# PilotPi_Sensors.net
KiCad netlist of a schematic drawn in Altium Designer
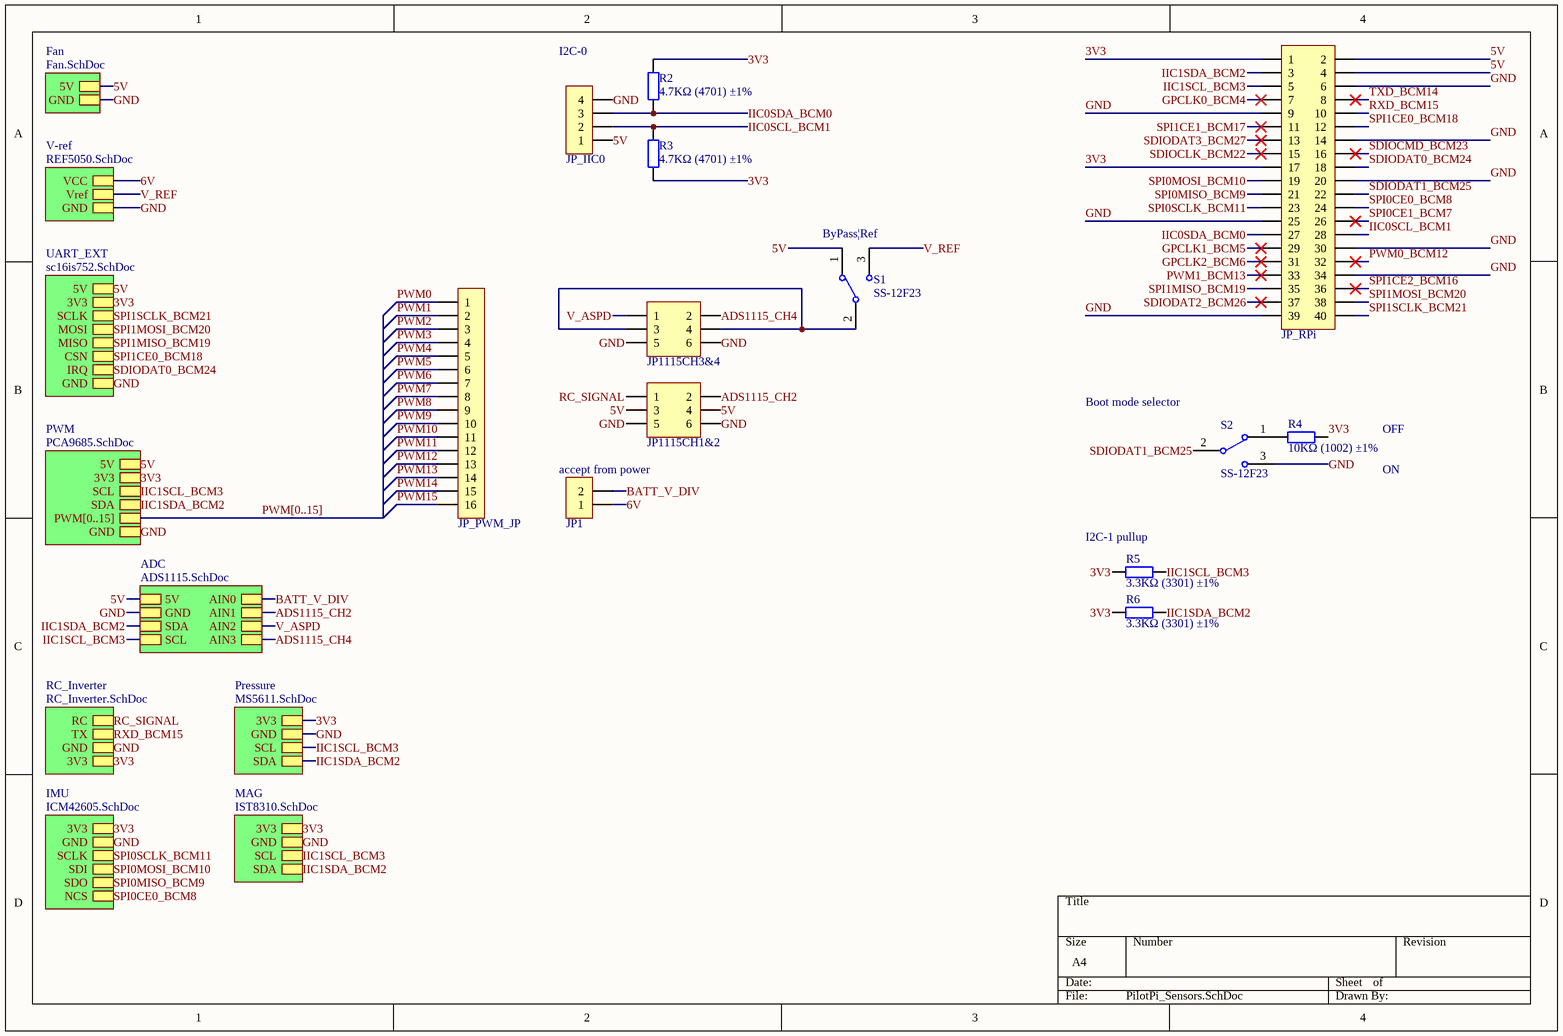
[diagram p0: PilotPi_Sensors.SchDoc]

(export (version "E")
  (design (tool "Eeschema 10.0.6"))
  (components
    (comp (ref "JP1")
      (value "HDR-1X2")
      (footprint "HDR2.54-LI-2P")
      (description "2P接插件")
      (fields (field (name "版权归属") "源创客"))
      (libsource (lib "4.5   - 接插件-脚距2.54") (part "Header 2"))
    )
    (comp (ref "JP1115CH1&2")
      (value "Header3X2")
      (footprint "HDR2.54-WI-2x3P")
      (description "3*2P接插件")
      (fields (field (name "版权归属") "源创客"))
      (libsource (lib "4.5   - 接插件-脚距2.54") (part "Header 3X2"))
    )
    (comp (ref "JP1115CH3&4")
      (value "Header3X2")
      (footprint "HDR2.54-WI-2x3P")
      (description "3*2P接插件")
      (fields (field (name "版权归属") "源创客"))
      (libsource (lib "4.5   - 接插件-脚距2.54") (part "Header 3X2"))
    )
    (comp (ref "JP_IIC0")
      (value "HDR-1X4")
      (footprint "MX 1.25-WS-4P")
      (description "4P接插件")
      (fields (field (name "版权归属") "源创客"))
      (libsource (lib "4.2   - 接插件-脚距1.25") (part "Header 4"))
    )
    (comp (ref "JP_PWM_JP")
      (value "HDR-1X16")
      (footprint "HDR2.54-LI-16P")
      (description "16P接插件")
      (fields (field (name "版权归属") "源创客"))
      (libsource (lib "4.5   - 接插件-脚距2.54") (part "Header 16"))
    )
    (comp (ref "JP_RPi")
      (value "Header 2X11")
      (footprint "HDR2.54-LI-2x20P")
      (description "20*2P接插件")
      (fields (field (name "版权归属") "源创客"))
      (libsource (lib "4.5   - 接插件-脚距2.54") (part "Header 20X2"))
    )
    (comp (ref "R2")
      (value "4.7KΩ (4701) ±1%")
      (footprint "0402_R")
      (description "贴片电阻")
      (libsource (lib "Miscellaneous Devices LC") (part "0402 4.7KΩ (4701) 1%"))
    )
    (comp (ref "R3")
      (value "4.7KΩ (4701) ±1%")
      (footprint "0402_R")
      (description "贴片电阻")
      (libsource (lib "Miscellaneous Devices LC") (part "0402 4.7KΩ (4701) 1%"))
    )
    (comp (ref "R4")
      (value "10KΩ (1002) ±1%")
      (footprint "0402_R")
      (description "贴片电阻")
      (libsource (lib "Miscellaneous Devices LC") (part "0402 10KΩ (1002) 1%"))
    )
    (comp (ref "R5")
      (value "3.3KΩ (3301) ±1%")
      (footprint "0402_R")
      (description "贴片电阻")
      (libsource (lib "Miscellaneous Devices LC") (part "0402 3.3KΩ (3301) 1%"))
    )
    (comp (ref "R6")
      (value "3.3KΩ (3301) ±1%")
      (footprint "0402_R")
      (description "贴片电阻")
      (libsource (lib "Miscellaneous Devices LC") (part "0402 3.3KΩ (3301) 1%"))
    )
    (comp (ref "S1")
      (value "SS-12F23")
      (footprint "MSK-12C01-07")
      (description "1路波动开关")
      (fields (field (name "版权归属") "源创客"))
      (libsource (lib "5.1   - 按键-开关") (part "SSW-1P"))
    )
    (comp (ref "S2")
      (value "SS-12F23")
      (footprint "MSK-12C01-07")
      (description "1路波动开关")
      (fields (field (name "版权归属") "源创客"))
      (libsource (lib "5.1   - 按键-开关") (part "SSW-1P"))
    )
  )
  (nets
    (net (code "1") (name "/3V3") (class "Default")
      (node (ref "JP_RPi") (pin "1") (pinfunction "1_1") (pintype "passive"))
      (node (ref "JP_RPi") (pin "17") (pinfunction "17_17") (pintype "passive"))
      (node (ref "R2") (pin "2") (pinfunction "2_2") (pintype "passive"))
      (node (ref "R3") (pin "1") (pinfunction "1_1") (pintype "passive"))
      (node (ref "R4") (pin "2") (pinfunction "2_2") (pintype "passive"))
      (node (ref "R5") (pin "1") (pinfunction "1_1") (pintype "passive"))
      (node (ref "R6") (pin "1") (pinfunction "1_1") (pintype "passive"))
    )
    (net (code "2") (name "/5V") (class "Default")
      (node (ref "JP1115CH1&2") (pin "3") (pinfunction "3_3") (pintype "passive"))
      (node (ref "JP1115CH1&2") (pin "4") (pinfunction "4_4") (pintype "passive"))
      (node (ref "JP_IIC0") (pin "1") (pinfunction "1_1") (pintype "passive"))
      (node (ref "JP_RPi") (pin "2") (pinfunction "2_2") (pintype "passive"))
      (node (ref "JP_RPi") (pin "4") (pinfunction "4_4") (pintype "passive"))
      (node (ref "S1") (pin "1") (pinfunction "1_1") (pintype "passive"))
    )
    (net (code "3") (name "/6V") (class "Default")
      (node (ref "JP1") (pin "1") (pinfunction "1_1") (pintype "passive"))
    )
    (net (code "4") (name "/ADS1115_CH2") (class "Default")
      (node (ref "JP1115CH1&2") (pin "2") (pinfunction "2_2") (pintype "passive"))
    )
    (net (code "5") (name "/ADS1115_CH4") (class "Default")
      (node (ref "JP1115CH3&4") (pin "2") (pinfunction "2_2") (pintype "passive"))
    )
    (net (code "6") (name "/BATT_V_DIV") (class "Default")
      (node (ref "JP1") (pin "2") (pinfunction "2_2") (pintype "passive"))
    )
    (net (code "7") (name "/GND") (class "Default")
      (node (ref "JP1115CH1&2") (pin "5") (pinfunction "5_5") (pintype "passive"))
      (node (ref "JP1115CH1&2") (pin "6") (pinfunction "6_6") (pintype "passive"))
      (node (ref "JP1115CH3&4") (pin "5") (pinfunction "5_5") (pintype "passive"))
      (node (ref "JP1115CH3&4") (pin "6") (pinfunction "6_6") (pintype "passive"))
      (node (ref "JP_IIC0") (pin "4") (pinfunction "4_4") (pintype "passive"))
      (node (ref "JP_RPi") (pin "14") (pinfunction "14_14") (pintype "passive"))
      (node (ref "JP_RPi") (pin "20") (pinfunction "20_20") (pintype "passive"))
      (node (ref "JP_RPi") (pin "25") (pinfunction "25_25") (pintype "passive"))
      (node (ref "JP_RPi") (pin "30") (pinfunction "30_30") (pintype "passive"))
      (node (ref "JP_RPi") (pin "34") (pinfunction "34_34") (pintype "passive"))
      (node (ref "JP_RPi") (pin "39") (pinfunction "39_39") (pintype "passive"))
      (node (ref "JP_RPi") (pin "6") (pinfunction "6_6") (pintype "passive"))
      (node (ref "JP_RPi") (pin "9") (pinfunction "9_9") (pintype "passive"))
      (node (ref "S2") (pin "3") (pinfunction "3_3") (pintype "passive"))
    )
    (net (code "8") (name "/GPCLK0_BCM4") (class "Default")
      (node (ref "JP_RPi") (pin "7") (pinfunction "7_7") (pintype "passive+no_connect"))
    )
    (net (code "9") (name "/GPCLK1_BCM5") (class "Default")
      (node (ref "JP_RPi") (pin "29") (pinfunction "29_29") (pintype "passive+no_connect"))
    )
    (net (code "10") (name "/GPCLK2_BCM6") (class "Default")
      (node (ref "JP_RPi") (pin "31") (pinfunction "31_31") (pintype "passive+no_connect"))
    )
    (net (code "11") (name "/IIC0SCL_BCM1") (class "Default")
      (node (ref "JP_IIC0") (pin "2") (pinfunction "2_2") (pintype "passive"))
      (node (ref "JP_RPi") (pin "28") (pinfunction "28_28") (pintype "passive"))
      (node (ref "R3") (pin "2") (pinfunction "2_2") (pintype "passive"))
    )
    (net (code "12") (name "/IIC0SDA_BCM0") (class "Default")
      (node (ref "JP_IIC0") (pin "3") (pinfunction "3_3") (pintype "passive"))
      (node (ref "JP_RPi") (pin "27") (pinfunction "27_27") (pintype "passive"))
      (node (ref "R2") (pin "1") (pinfunction "1_1") (pintype "passive"))
    )
    (net (code "13") (name "/IIC1SCL_BCM3") (class "Default")
      (node (ref "JP_RPi") (pin "5") (pinfunction "5_5") (pintype "passive"))
      (node (ref "R5") (pin "2") (pinfunction "2_2") (pintype "passive"))
    )
    (net (code "14") (name "/IIC1SDA_BCM2") (class "Default")
      (node (ref "JP_RPi") (pin "3") (pinfunction "3_3") (pintype "passive"))
      (node (ref "R6") (pin "2") (pinfunction "2_2") (pintype "passive"))
    )
    (net (code "15") (name "/PWM0") (class "Default")
      (node (ref "JP_PWM_JP") (pin "1") (pinfunction "1_1") (pintype "passive"))
    )
    (net (code "16") (name "/PWM0_BCM12") (class "Default")
      (node (ref "JP_RPi") (pin "32") (pinfunction "32_32") (pintype "passive+no_connect"))
    )
    (net (code "17") (name "/PWM1") (class "Default")
      (node (ref "JP_PWM_JP") (pin "2") (pinfunction "2_2") (pintype "passive"))
    )
    (net (code "18") (name "/PWM1_BCM13") (class "Default")
      (node (ref "JP_RPi") (pin "33") (pinfunction "33_33") (pintype "passive+no_connect"))
    )
    (net (code "19") (name "/PWM2") (class "Default")
      (node (ref "JP_PWM_JP") (pin "3") (pinfunction "3_3") (pintype "passive"))
    )
    (net (code "20") (name "/PWM3") (class "Default")
      (node (ref "JP_PWM_JP") (pin "4") (pinfunction "4_4") (pintype "passive"))
    )
    (net (code "21") (name "/PWM4") (class "Default")
      (node (ref "JP_PWM_JP") (pin "5") (pinfunction "5_5") (pintype "passive"))
    )
    (net (code "22") (name "/PWM5") (class "Default")
      (node (ref "JP_PWM_JP") (pin "6") (pinfunction "6_6") (pintype "passive"))
    )
    (net (code "23") (name "/PWM6") (class "Default")
      (node (ref "JP_PWM_JP") (pin "7") (pinfunction "7_7") (pintype "passive"))
    )
    (net (code "24") (name "/PWM7") (class "Default")
      (node (ref "JP_PWM_JP") (pin "8") (pinfunction "8_8") (pintype "passive"))
    )
    (net (code "25") (name "/PWM8") (class "Default")
      (node (ref "JP_PWM_JP") (pin "9") (pinfunction "9_9") (pintype "passive"))
    )
    (net (code "26") (name "/PWM9") (class "Default")
      (node (ref "JP_PWM_JP") (pin "10") (pinfunction "10_10") (pintype "passive"))
    )
    (net (code "27") (name "/PWM10") (class "Default")
      (node (ref "JP_PWM_JP") (pin "11") (pinfunction "11_11") (pintype "passive"))
    )
    (net (code "28") (name "/PWM11") (class "Default")
      (node (ref "JP_PWM_JP") (pin "12") (pinfunction "12_12") (pintype "passive"))
    )
    (net (code "29") (name "/PWM12") (class "Default")
      (node (ref "JP_PWM_JP") (pin "13") (pinfunction "13_13") (pintype "passive"))
    )
    (net (code "30") (name "/PWM13") (class "Default")
      (node (ref "JP_PWM_JP") (pin "14") (pinfunction "14_14") (pintype "passive"))
    )
    (net (code "31") (name "/PWM14") (class "Default")
      (node (ref "JP_PWM_JP") (pin "15") (pinfunction "15_15") (pintype "passive"))
    )
    (net (code "32") (name "/PWM15") (class "Default")
      (node (ref "JP_PWM_JP") (pin "16") (pinfunction "16_16") (pintype "passive"))
    )
    (net (code "34") (name "/RC_SIGNAL") (class "Default")
      (node (ref "JP1115CH1&2") (pin "1") (pinfunction "1_1") (pintype "passive"))
    )
    (net (code "35") (name "/RXD_BCM15") (class "Default")
      (node (ref "JP_RPi") (pin "10") (pinfunction "10_10") (pintype "passive"))
    )
    (net (code "36") (name "/SDIOCLK_BCM22") (class "Default")
      (node (ref "JP_RPi") (pin "15") (pinfunction "15_15") (pintype "passive+no_connect"))
    )
    (net (code "37") (name "/SDIOCMD_BCM23") (class "Default")
      (node (ref "JP_RPi") (pin "16") (pinfunction "16_16") (pintype "passive+no_connect"))
    )
    (net (code "38") (name "/SDIODAT0_BCM24") (class "Default")
      (node (ref "JP_RPi") (pin "18") (pinfunction "18_18") (pintype "passive"))
    )
    (net (code "39") (name "/SDIODAT1_BCM25") (class "Default")
      (node (ref "JP_RPi") (pin "22") (pinfunction "22_22") (pintype "passive"))
      (node (ref "S2") (pin "2") (pinfunction "2_2") (pintype "passive"))
    )
    (net (code "40") (name "/SDIODAT2_BCM26") (class "Default")
      (node (ref "JP_RPi") (pin "37") (pinfunction "37_37") (pintype "passive+no_connect"))
    )
    (net (code "41") (name "/SDIODAT3_BCM27") (class "Default")
      (node (ref "JP_RPi") (pin "13") (pinfunction "13_13") (pintype "passive+no_connect"))
    )
    (net (code "42") (name "/SPI0CE0_BCM8") (class "Default")
      (node (ref "JP_RPi") (pin "24") (pinfunction "24_24") (pintype "passive"))
    )
    (net (code "43") (name "/SPI0CE1_BCM7") (class "Default")
      (node (ref "JP_RPi") (pin "26") (pinfunction "26_26") (pintype "passive+no_connect"))
    )
    (net (code "44") (name "/SPI0MISO_BCM9") (class "Default")
      (node (ref "JP_RPi") (pin "21") (pinfunction "21_21") (pintype "passive"))
    )
    (net (code "45") (name "/SPI0MOSI_BCM10") (class "Default")
      (node (ref "JP_RPi") (pin "19") (pinfunction "19_19") (pintype "passive"))
    )
    (net (code "46") (name "/SPI0SCLK_BCM11") (class "Default")
      (node (ref "JP_RPi") (pin "23") (pinfunction "23_23") (pintype "passive"))
    )
    (net (code "47") (name "/SPI1CE0_BCM18") (class "Default")
      (node (ref "JP_RPi") (pin "12") (pinfunction "12_12") (pintype "passive"))
    )
    (net (code "48") (name "/SPI1CE1_BCM17") (class "Default")
      (node (ref "JP_RPi") (pin "11") (pinfunction "11_11") (pintype "passive+no_connect"))
    )
    (net (code "49") (name "/SPI1CE2_BCM16") (class "Default")
      (node (ref "JP_RPi") (pin "36") (pinfunction "36_36") (pintype "passive+no_connect"))
    )
    (net (code "50") (name "/SPI1MISO_BCM19") (class "Default")
      (node (ref "JP_RPi") (pin "35") (pinfunction "35_35") (pintype "passive"))
    )
    (net (code "51") (name "/SPI1MOSI_BCM20") (class "Default")
      (node (ref "JP_RPi") (pin "38") (pinfunction "38_38") (pintype "passive"))
    )
    (net (code "52") (name "/SPI1SCLK_BCM21") (class "Default")
      (node (ref "JP_RPi") (pin "40") (pinfunction "40_40") (pintype "passive"))
    )
    (net (code "53") (name "/TXD_BCM14") (class "Default")
      (node (ref "JP_RPi") (pin "8") (pinfunction "8_8") (pintype "passive+no_connect"))
    )
    (net (code "54") (name "/V_ASPD") (class "Default")
      (node (ref "JP1115CH3&4") (pin "1") (pinfunction "1_1") (pintype "passive"))
    )
    (net (code "55") (name "/V_REF") (class "Default")
      (node (ref "S1") (pin "3") (pinfunction "3_3") (pintype "passive"))
    )
    (net (code "56") (name "Net-(JP1115CH3&4-Pad3)") (class "Default")
      (node (ref "JP1115CH3&4") (pin "3") (pinfunction "3_3") (pintype "passive"))
      (node (ref "JP1115CH3&4") (pin "4") (pinfunction "4_4") (pintype "passive"))
      (node (ref "S1") (pin "2") (pinfunction "2_2") (pintype "passive"))
    )
    (net (code "57") (name "Net-(R4-Pad1)") (class "Default")
      (node (ref "R4") (pin "1") (pinfunction "1_1") (pintype "passive"))
      (node (ref "S2") (pin "1") (pinfunction "1_1") (pintype "passive"))
    )
  )
)
